# 1_PIC.net
KiCad netlist of a schematic drawn in Altium Designer
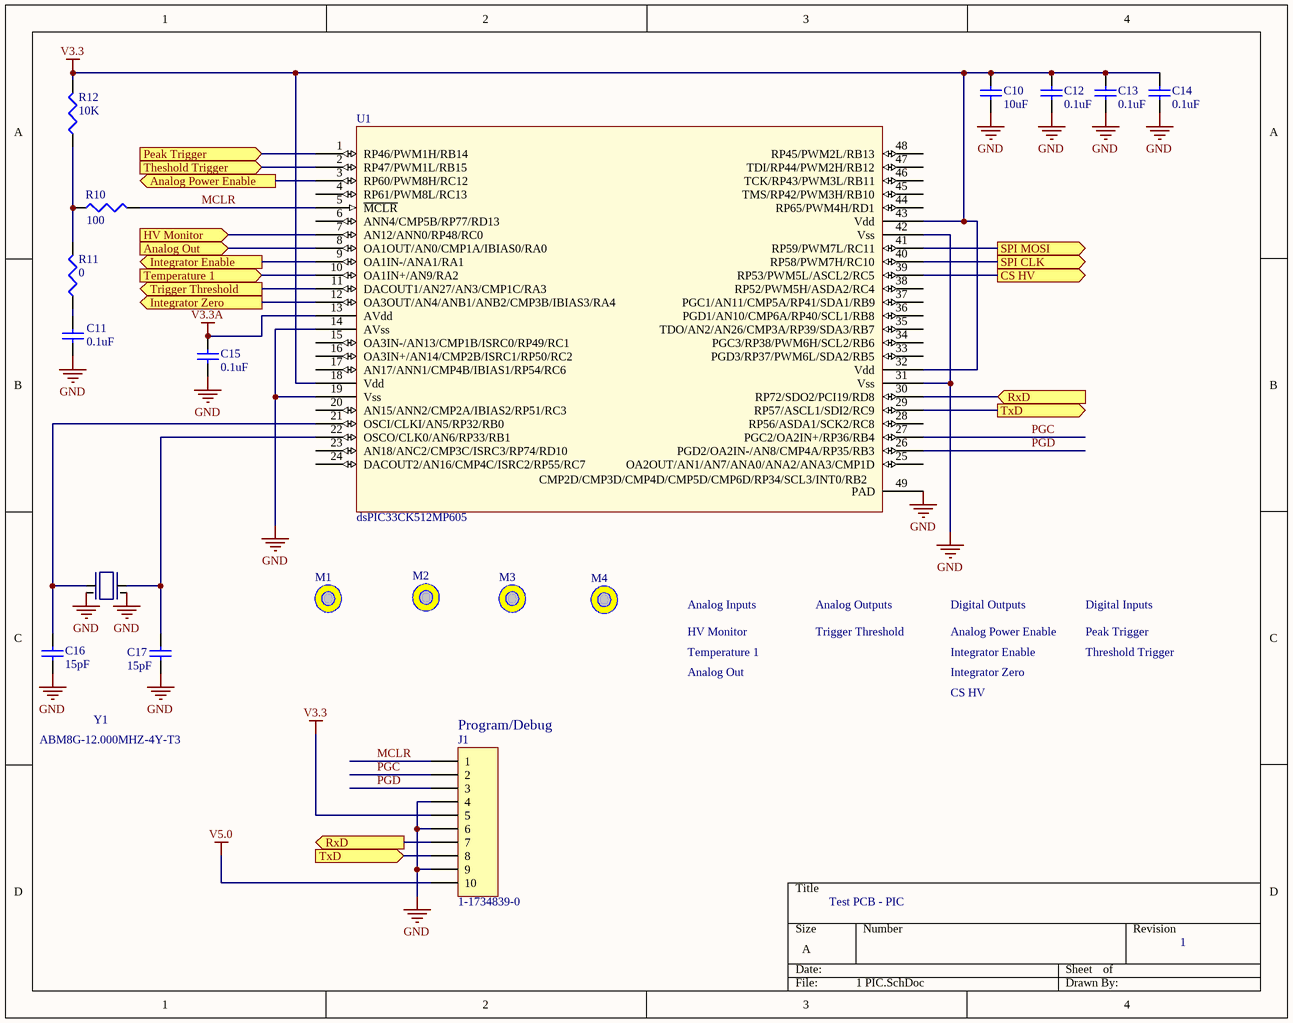
[diagram p0: 1 PIC.SchDoc]

(export (version "E")
  (design (tool "Eeschema 10.0.6"))
  (components
    (comp (ref "C10")
      (value "10uF")
      (footprint "C0805")
      (description "Capacitor, SM")
      (fields (field (name "PUBLISHER") "Altium Limited"))
      (libsource (lib "Graylark") (part "Cap SM"))
    )
    (comp (ref "C11")
      (value "0.1uF")
      (footprint "C0402")
      (description "Capacitor, SM")
      (fields (field (name "PUBLISHER") "Altium Limited"))
      (libsource (lib "Graylark") (part "Cap SM"))
    )
    (comp (ref "C12")
      (value "0.1uF")
      (footprint "C0402")
      (description "Capacitor, SM")
      (fields (field (name "PUBLISHER") "Altium Limited"))
      (libsource (lib "Graylark") (part "Cap SM"))
    )
    (comp (ref "C13")
      (value "0.1uF")
      (footprint "C0402")
      (description "Capacitor, SM")
      (fields (field (name "PUBLISHER") "Altium Limited"))
      (libsource (lib "Graylark") (part "Cap SM"))
    )
    (comp (ref "C14")
      (value "0.1uF")
      (footprint "C0402")
      (description "Capacitor, SM")
      (fields (field (name "PUBLISHER") "Altium Limited"))
      (libsource (lib "Graylark") (part "Cap SM"))
    )
    (comp (ref "C15")
      (value "0.1uF")
      (footprint "C0402")
      (description "Capacitor, SM")
      (fields (field (name "PUBLISHER") "Altium Limited"))
      (libsource (lib "Graylark") (part "Cap SM"))
    )
    (comp (ref "C16")
      (value "15pF")
      (footprint "C0603")
      (description "Capacitor, SM")
      (fields (field (name "PUBLISHER") "Altium Limited"))
      (libsource (lib "Graylark") (part "Cap SM"))
    )
    (comp (ref "C17")
      (value "15pF")
      (footprint "C0603")
      (description "Capacitor, SM")
      (fields (field (name "PUBLISHER") "Altium Limited"))
      (libsource (lib "Graylark") (part "Cap SM"))
    )
    (comp (ref "J1")
      (value "1-1734839-0")
      (footprint "1-1734839-0")
      (description "Header 10")
      (fields (field (name "PUBLISHER") "Altium Limited"))
      (libsource (lib "Graylark") (part "Header 10"))
    )
    (comp (ref "M1")
      (value "Mounting Hole")
      (footprint "Mounting Hole 0-80")
      (libsource (lib "Graylark") (part "Mounting Hole"))
    )
    (comp (ref "M2")
      (value "Mounting Hole")
      (footprint "Mounting Hole 0-80")
      (libsource (lib "Graylark") (part "Mounting Hole"))
    )
    (comp (ref "M3")
      (value "Mounting Hole")
      (footprint "Mounting Hole 0-80")
      (libsource (lib "Graylark") (part "Mounting Hole"))
    )
    (comp (ref "M4")
      (value "Mounting Hole")
      (footprint "Mounting Hole 0-80")
      (libsource (lib "Graylark") (part "Mounting Hole"))
    )
    (comp (ref "R10")
      (value "100")
      (footprint "R0603")
      (description "Resistor")
      (fields (field (name "PUBLISHER") "Altium Limited"))
      (libsource (lib "Graylark") (part "Res SM"))
    )
    (comp (ref "R11")
      (value "0")
      (footprint "R0603")
      (description "Resistor")
      (fields (field (name "PUBLISHER") "Altium Limited"))
      (libsource (lib "Graylark") (part "Res SM"))
    )
    (comp (ref "R12")
      (value "10K")
      (footprint "R0603")
      (description "Resistor")
      (fields (field (name "PUBLISHER") "Altium Limited"))
      (libsource (lib "Graylark") (part "Res SM"))
    )
    (comp (ref "U1")
      (value "dsPIC33CK512MP605")
      (footprint "QFN40P600X600X90_HS-49N")
      (description "Microcontroller")
      (libsource (lib "Graylark_new") (part "dsPIC33CK512MP605"))
    )
    (comp (ref "Y1")
      (value "ABM8G-12.000MHZ-4Y-T3")
      (footprint "7M Series XTAL")
      (libsource (lib "Graylark") (part "Crystal 4 Terminal"))
    )
  )
  (nets
    (net (code "1") (name "/Analog Out") (class "Default")
      (node (ref "U1") (pin "8") (pinfunction "OA1OUT/AN0/CMP1A/IBIAS0/RA0_8") (pintype "bidirectional"))
    )
    (net (code "2") (name "/Analog Power Enable") (class "Default")
      (node (ref "U1") (pin "3") (pinfunction "RP60/PWM8H/RC12_3") (pintype "bidirectional"))
    )
    (net (code "3") (name "/CS HV") (class "Default")
      (node (ref "U1") (pin "39") (pinfunction "RP53/PWM5L/ASCL2/RC5_39") (pintype "bidirectional"))
    )
    (net (code "4") (name "/HV Monitor") (class "Default")
      (node (ref "U1") (pin "7") (pinfunction "AN12/ANN0/RP48/RC0_7") (pintype "bidirectional"))
    )
    (net (code "5") (name "/Integrator Enable") (class "Default")
      (node (ref "U1") (pin "9") (pinfunction "OA1IN-/ANA1/RA1_9") (pintype "bidirectional"))
    )
    (net (code "6") (name "/Integrator Zero") (class "Default")
      (node (ref "U1") (pin "12") (pinfunction "OA3OUT/AN4/ANB1/ANB2/CMP3B/IBIAS3/RA4_12") (pintype "bidirectional"))
    )
    (net (code "7") (name "/MCLR") (class "Default")
      (node (ref "J1") (pin "1") (pinfunction "1_1") (pintype "passive"))
      (node (ref "R10") (pin "2") (pinfunction "2_2") (pintype "passive"))
      (node (ref "U1") (pin "5") (pinfunction "~{MCLR}_5") (pintype "input"))
    )
    (net (code "8") (name "/PGC") (class "Default")
      (node (ref "J1") (pin "2") (pinfunction "2_2") (pintype "passive"))
      (node (ref "U1") (pin "27") (pinfunction "PGC2/OA2IN+/RP36/RB4_27") (pintype "bidirectional"))
    )
    (net (code "9") (name "/PGD") (class "Default")
      (node (ref "J1") (pin "3") (pinfunction "3_3") (pintype "passive"))
      (node (ref "U1") (pin "26") (pinfunction "PGD2/OA2IN-/AN8/CMP4A/RP35/RB3_26") (pintype "bidirectional"))
    )
    (net (code "10") (name "/Peak Trigger") (class "Default")
      (node (ref "U1") (pin "1") (pinfunction "RP46/PWM1H/RB14_1") (pintype "bidirectional"))
    )
    (net (code "11") (name "/RxD") (class "Default")
      (node (ref "J1") (pin "7") (pinfunction "7_7") (pintype "passive"))
      (node (ref "U1") (pin "30") (pinfunction "RP72/SDO2/PCI19/RD8_30") (pintype "bidirectional"))
    )
    (net (code "12") (name "/SPI CLK") (class "Default")
      (node (ref "U1") (pin "40") (pinfunction "RP58/PWM7H/RC10_40") (pintype "bidirectional"))
    )
    (net (code "13") (name "/SPI MOSI") (class "Default")
      (node (ref "U1") (pin "41") (pinfunction "RP59/PWM7L/RC11_41") (pintype "bidirectional"))
    )
    (net (code "14") (name "/Temperature 1") (class "Default")
      (node (ref "U1") (pin "10") (pinfunction "OA1IN+/AN9/RA2_10") (pintype "bidirectional"))
    )
    (net (code "15") (name "/Theshold Trigger") (class "Default")
      (node (ref "U1") (pin "2") (pinfunction "RP47/PWM1L/RB15_2") (pintype "bidirectional"))
    )
    (net (code "16") (name "/Trigger Threshold") (class "Default")
      (node (ref "U1") (pin "11") (pinfunction "DACOUT1/AN27/AN3/CMP1C/RA3_11") (pintype "bidirectional"))
    )
    (net (code "17") (name "/TxD") (class "Default")
      (node (ref "J1") (pin "8") (pinfunction "8_8") (pintype "passive"))
      (node (ref "U1") (pin "29") (pinfunction "RP57/ASCL1/SDI2/RC9_29") (pintype "bidirectional"))
    )
    (net (code "18") (name "GND") (class "Default")
      (node (ref "C10") (pin "1") (pinfunction "1_1") (pintype "passive"))
      (node (ref "C11") (pin "1") (pinfunction "1_1") (pintype "passive"))
      (node (ref "C12") (pin "1") (pinfunction "1_1") (pintype "passive"))
      (node (ref "C13") (pin "1") (pinfunction "1_1") (pintype "passive"))
      (node (ref "C14") (pin "1") (pinfunction "1_1") (pintype "passive"))
      (node (ref "C15") (pin "1") (pinfunction "1_1") (pintype "passive"))
      (node (ref "C16") (pin "1") (pinfunction "1_1") (pintype "passive"))
      (node (ref "C17") (pin "1") (pinfunction "1_1") (pintype "passive"))
      (node (ref "J1") (pin "4") (pinfunction "4_4") (pintype "passive"))
      (node (ref "J1") (pin "6") (pinfunction "6_6") (pintype "passive"))
      (node (ref "J1") (pin "9") (pinfunction "9_9") (pintype "passive"))
      (node (ref "U1") (pin "14") (pinfunction "AVss_14") (pintype "power_in"))
      (node (ref "U1") (pin "19") (pinfunction "Vss_19") (pintype "power_in"))
      (node (ref "U1") (pin "31") (pinfunction "Vss_31") (pintype "power_in"))
      (node (ref "U1") (pin "42") (pinfunction "Vss_42") (pintype "power_in"))
      (node (ref "U1") (pin "49") (pinfunction "PAD_49") (pintype "passive"))
      (node (ref "Y1") (pin "2") (pinfunction "2_2") (pintype "passive"))
      (node (ref "Y1") (pin "4") (pinfunction "4_4") (pintype "passive"))
    )
    (net (code "19") (name "Net-(C11-Pad2)") (class "Default")
      (node (ref "C11") (pin "2") (pinfunction "2_2") (pintype "passive"))
      (node (ref "R11") (pin "1") (pinfunction "1_1") (pintype "passive"))
    )
    (net (code "20") (name "Net-(R10-Pad1)") (class "Default")
      (node (ref "R10") (pin "1") (pinfunction "1_1") (pintype "passive"))
      (node (ref "R11") (pin "2") (pinfunction "2_2") (pintype "passive"))
      (node (ref "R12") (pin "1") (pinfunction "1_1") (pintype "passive"))
    )
    (net (code "21") (name "Net-(U1-OSCI{slash}CLKI{slash}AN5{slash}RP32{slash}RB0)") (class "Default")
      (node (ref "C16") (pin "2") (pinfunction "2_2") (pintype "passive"))
      (node (ref "U1") (pin "21") (pinfunction "OSCI/CLKI/AN5/RP32/RB0_21") (pintype "bidirectional"))
      (node (ref "Y1") (pin "1") (pinfunction "1_1") (pintype "passive"))
    )
    (net (code "22") (name "Net-(U1-OSCO{slash}CLK0{slash}AN6{slash}RP33{slash}RB1)") (class "Default")
      (node (ref "C17") (pin "2") (pinfunction "2_2") (pintype "passive"))
      (node (ref "U1") (pin "22") (pinfunction "OSCO/CLK0/AN6/RP33/RB1_22") (pintype "bidirectional"))
      (node (ref "Y1") (pin "3") (pinfunction "3_3") (pintype "passive"))
    )
    (net (code "23") (name "V3.3") (class "Default")
      (node (ref "C10") (pin "2") (pinfunction "2_2") (pintype "passive"))
      (node (ref "C12") (pin "2") (pinfunction "2_2") (pintype "passive"))
      (node (ref "C13") (pin "2") (pinfunction "2_2") (pintype "passive"))
      (node (ref "C14") (pin "2") (pinfunction "2_2") (pintype "passive"))
      (node (ref "J1") (pin "5") (pinfunction "5_5") (pintype "passive"))
      (node (ref "R12") (pin "2") (pinfunction "2_2") (pintype "passive"))
      (node (ref "U1") (pin "18") (pinfunction "Vdd_18") (pintype "power_in"))
      (node (ref "U1") (pin "32") (pinfunction "Vdd_32") (pintype "power_in"))
      (node (ref "U1") (pin "43") (pinfunction "Vdd_43") (pintype "power_in"))
    )
    (net (code "24") (name "V3.3A") (class "Default")
      (node (ref "C15") (pin "2") (pinfunction "2_2") (pintype "passive"))
      (node (ref "U1") (pin "13") (pinfunction "AVdd_13") (pintype "power_in"))
    )
    (net (code "25") (name "V5.0") (class "Default")
      (node (ref "J1") (pin "10") (pinfunction "10_10") (pintype "passive"))
    )
    (net (code "26") (name "unconnected-(U1-AN15{slash}ANN2{slash}CMP2A{slash}IBIAS2{slash}RP51{slash}RC3-Pad20)") (class "Default")
      (node (ref "U1") (pin "20") (pinfunction "AN15/ANN2/CMP2A/IBIAS2/RP51/RC3_20") (pintype "bidirectional"))
    )
    (net (code "27") (name "unconnected-(U1-AN17{slash}ANN1{slash}CMP4B{slash}IBIAS1{slash}RP54{slash}RC6-Pad17)") (class "Default")
      (node (ref "U1") (pin "17") (pinfunction "AN17/ANN1/CMP4B/IBIAS1/RP54/RC6_17") (pintype "bidirectional"))
    )
    (net (code "28") (name "unconnected-(U1-AN18{slash}ANC2{slash}CMP3C{slash}ISRC3{slash}RP74{slash}RD10-Pad23)") (class "Default")
      (node (ref "U1") (pin "23") (pinfunction "AN18/ANC2/CMP3C/ISRC3/RP74/RD10_23") (pintype "bidirectional"))
    )
    (net (code "29") (name "unconnected-(U1-ANN4{slash}CMP5B{slash}RP77{slash}RD13-Pad6)") (class "Default")
      (node (ref "U1") (pin "6") (pinfunction "ANN4/CMP5B/RP77/RD13_6") (pintype "bidirectional"))
    )
    (net (code "30") (name "unconnected-(U1-DACOUT2{slash}AN16{slash}CMP4C{slash}ISRC2{slash}RP55{slash}RC7-Pad24)") (class "Default")
      (node (ref "U1") (pin "24") (pinfunction "DACOUT2/AN16/CMP4C/ISRC2/RP55/RC7_24") (pintype "bidirectional"))
    )
    (net (code "31") (name "unconnected-(U1-OA2OUT{slash}AN1{slash}AN7{slash}ANA0{slash}ANA2{slash}ANA3{slash}CMP1D-Pad25)") (class "Default")
      (node (ref "U1") (pin "25") (pinfunction "OA2OUT/AN1/AN7/ANA0/ANA2/ANA3/CMP1D_25") (pintype "bidirectional"))
    )
    (net (code "32") (name "unconnected-(U1-OA3IN+{slash}AN14{slash}CMP2B{slash}ISRC1{slash}RP50{slash}RC2-Pad16)") (class "Default")
      (node (ref "U1") (pin "16") (pinfunction "OA3IN+/AN14/CMP2B/ISRC1/RP50/RC2_16") (pintype "bidirectional"))
    )
    (net (code "33") (name "unconnected-(U1-OA3IN-{slash}AN13{slash}CMP1B{slash}ISRC0{slash}RP49{slash}RC1-Pad15)") (class "Default")
      (node (ref "U1") (pin "15") (pinfunction "OA3IN-/AN13/CMP1B/ISRC0/RP49/RC1_15") (pintype "bidirectional"))
    )
    (net (code "34") (name "unconnected-(U1-PGC1{slash}AN11{slash}CMP5A{slash}RP41{slash}SDA1{slash}RB9-Pad37)") (class "Default")
      (node (ref "U1") (pin "37") (pinfunction "PGC1/AN11/CMP5A/RP41/SDA1/RB9_37") (pintype "bidirectional"))
    )
    (net (code "35") (name "unconnected-(U1-PGC3{slash}RP38{slash}PWM6H{slash}SCL2{slash}RB6-Pad34)") (class "Default")
      (node (ref "U1") (pin "34") (pinfunction "PGC3/RP38/PWM6H/SCL2/RB6_34") (pintype "bidirectional"))
    )
    (net (code "36") (name "unconnected-(U1-PGD1{slash}AN10{slash}CMP6A{slash}RP40{slash}SCL1{slash}RB8-Pad36)") (class "Default")
      (node (ref "U1") (pin "36") (pinfunction "PGD1/AN10/CMP6A/RP40/SCL1/RB8_36") (pintype "bidirectional"))
    )
    (net (code "37") (name "unconnected-(U1-PGD3{slash}RP37{slash}PWM6L{slash}SDA2{slash}RB5-Pad33)") (class "Default")
      (node (ref "U1") (pin "33") (pinfunction "PGD3/RP37/PWM6L/SDA2/RB5_33") (pintype "bidirectional"))
    )
    (net (code "38") (name "unconnected-(U1-RP45{slash}PWM2L{slash}RB13-Pad48)") (class "Default")
      (node (ref "U1") (pin "48") (pinfunction "RP45/PWM2L/RB13_48") (pintype "bidirectional"))
    )
    (net (code "39") (name "unconnected-(U1-RP52{slash}PWM5H{slash}ASDA2{slash}RC4-Pad38)") (class "Default")
      (node (ref "U1") (pin "38") (pinfunction "RP52/PWM5H/ASDA2/RC4_38") (pintype "bidirectional"))
    )
    (net (code "40") (name "unconnected-(U1-RP56{slash}ASDA1{slash}SCK2{slash}RC8-Pad28)") (class "Default")
      (node (ref "U1") (pin "28") (pinfunction "RP56/ASDA1/SCK2/RC8_28") (pintype "bidirectional"))
    )
    (net (code "41") (name "unconnected-(U1-RP61{slash}PWM8L{slash}RC13-Pad4)") (class "Default")
      (node (ref "U1") (pin "4") (pinfunction "RP61/PWM8L/RC13_4") (pintype "bidirectional"))
    )
    (net (code "42") (name "unconnected-(U1-RP65{slash}PWM4H{slash}RD1-Pad44)") (class "Default")
      (node (ref "U1") (pin "44") (pinfunction "RP65/PWM4H/RD1_44") (pintype "bidirectional"))
    )
    (net (code "43") (name "unconnected-(U1-TCK{slash}RP43{slash}PWM3L{slash}RB11-Pad46)") (class "Default")
      (node (ref "U1") (pin "46") (pinfunction "TCK/RP43/PWM3L/RB11_46") (pintype "bidirectional"))
    )
    (net (code "44") (name "unconnected-(U1-TDI{slash}RP44{slash}PWM2H{slash}RB12-Pad47)") (class "Default")
      (node (ref "U1") (pin "47") (pinfunction "TDI/RP44/PWM2H/RB12_47") (pintype "bidirectional"))
    )
    (net (code "45") (name "unconnected-(U1-TDO{slash}AN2{slash}AN26{slash}CMP3A{slash}RP39{slash}SDA3{slash}RB7-Pad35)") (class "Default")
      (node (ref "U1") (pin "35") (pinfunction "TDO/AN2/AN26/CMP3A/RP39/SDA3/RB7_35") (pintype "bidirectional"))
    )
    (net (code "46") (name "unconnected-(U1-TMS{slash}RP42{slash}PWM3H{slash}RB10-Pad45)") (class "Default")
      (node (ref "U1") (pin "45") (pinfunction "TMS/RP42/PWM3H/RB10_45") (pintype "bidirectional"))
    )
  )
)
